# board.net
KiCad netlist of a schematic drawn in EAGLE
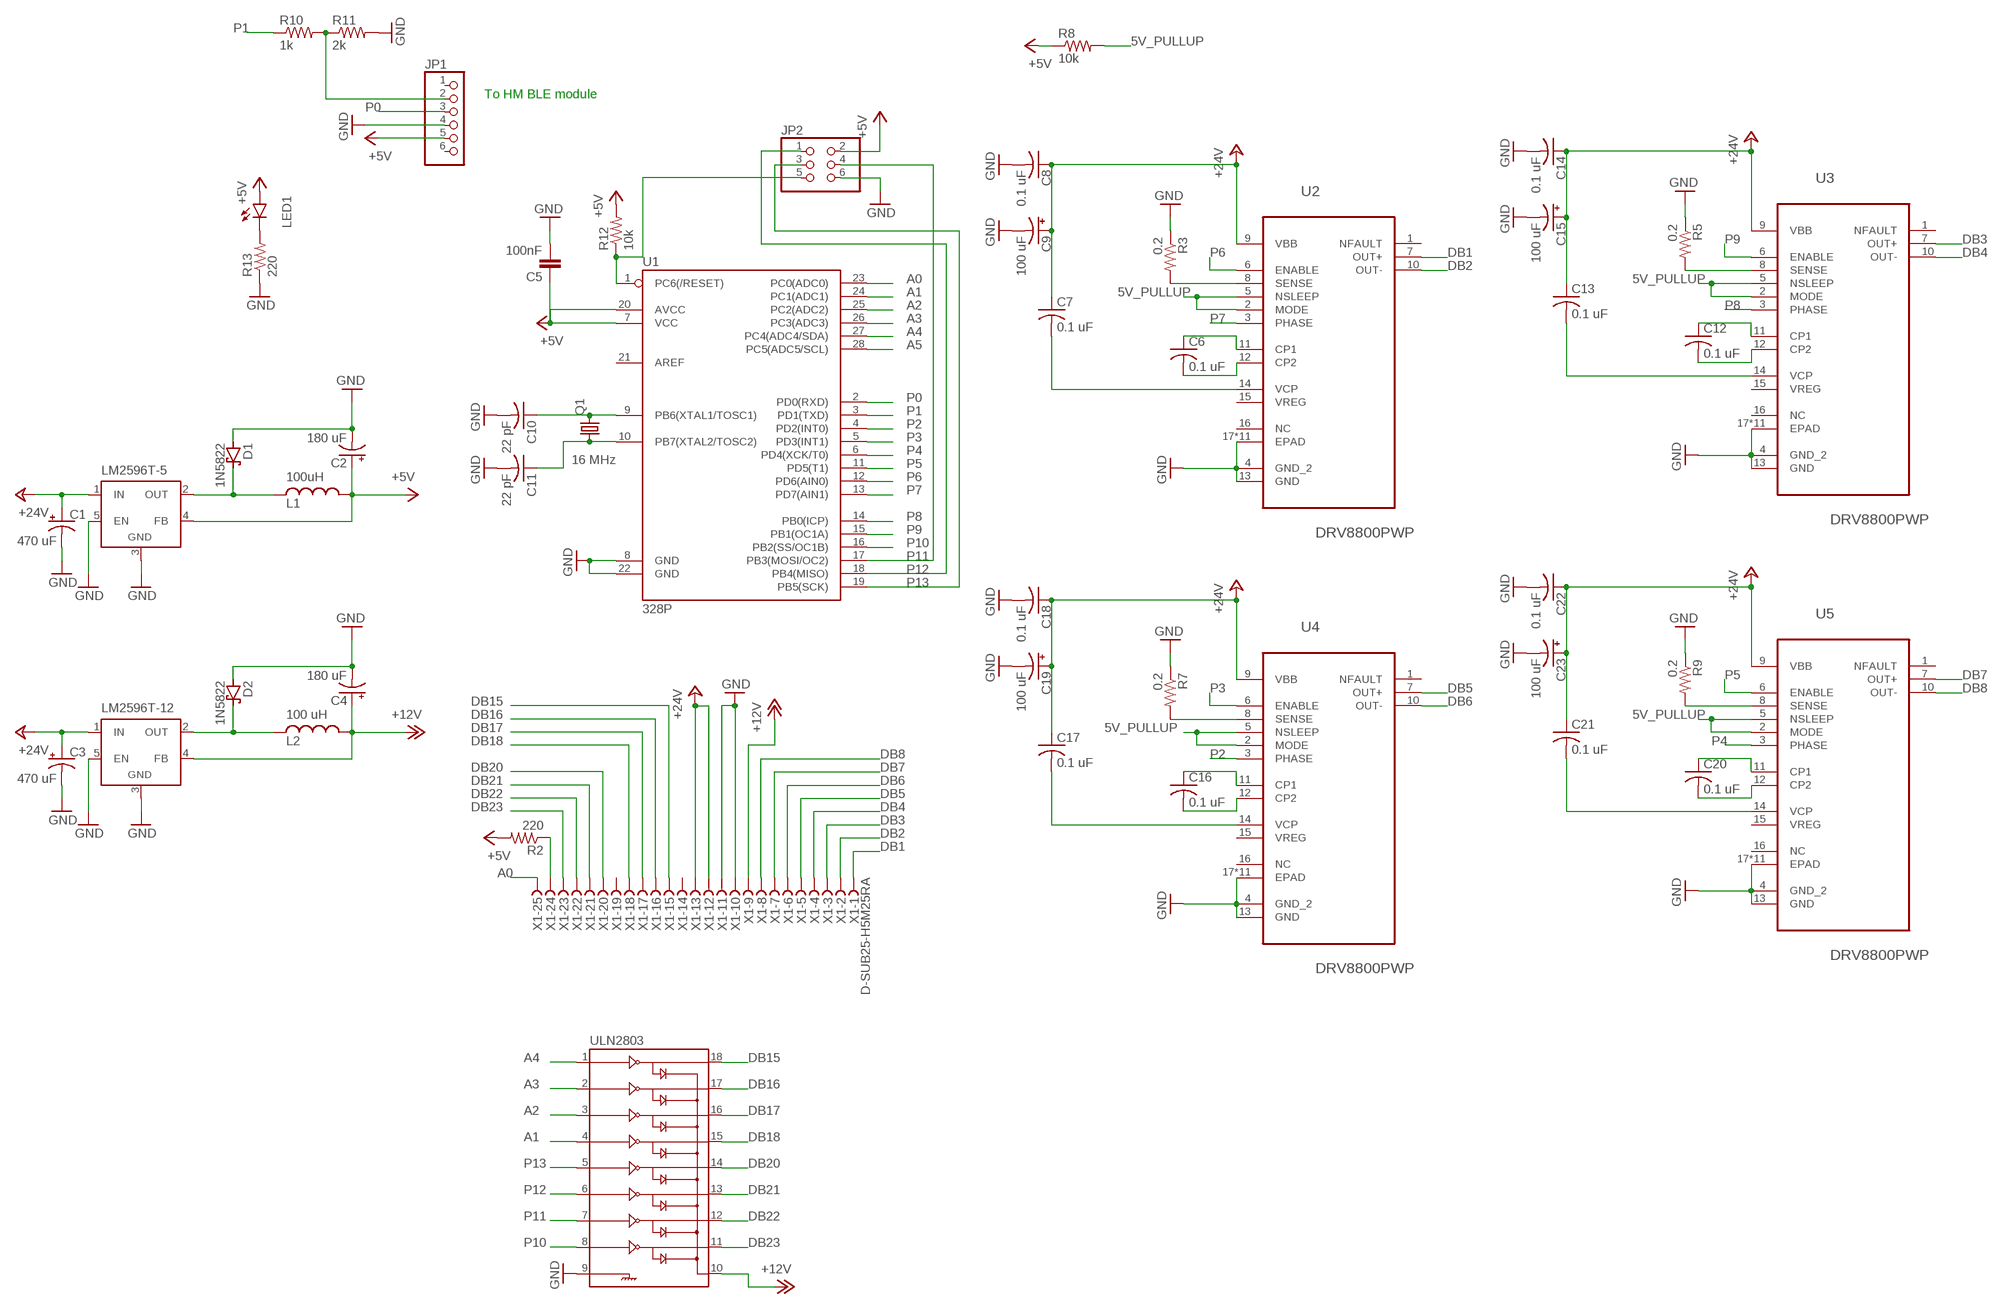
[diagram p0: schematic, sheet 1]

(export (version "E")
  (design (tool "Eeschema 10.0.6"))
  (components
    (comp (ref "C1")
      (value "470 uF")
      (footprint "eagle-import:E3,5-8")
      (libsource (lib "eagle-import") (part "CPOL-USE3.5-8"))
    )
    (comp (ref "C2")
      (value "180 uF")
      (footprint "eagle-import:E3,5-8")
      (libsource (lib "eagle-import") (part "CPOL-USE3.5-8"))
    )
    (comp (ref "C3")
      (value "470 uF")
      (footprint "eagle-import:E3,5-8")
      (libsource (lib "eagle-import") (part "CPOL-USE3.5-8"))
    )
    (comp (ref "C4")
      (value "180 uF")
      (footprint "eagle-import:E3,5-8")
      (libsource (lib "eagle-import") (part "CPOL-USE3.5-8"))
    )
    (comp (ref "C5")
      (value "100nF")
      (footprint "eagle-import:C0805")
      (libsource (lib "eagle-import") (part "C-EUC0805"))
    )
    (comp (ref "C6")
      (value "0.1 uF")
      (footprint "eagle-import:C0805")
      (libsource (lib "eagle-import") (part "C-USC0805"))
    )
    (comp (ref "C7")
      (value "0.1 uF")
      (footprint "eagle-import:C0805")
      (libsource (lib "eagle-import") (part "C-USC0805"))
    )
    (comp (ref "C8")
      (value "0.1 uF")
      (footprint "eagle-import:C0805")
      (libsource (lib "eagle-import") (part "C-USC0805"))
    )
    (comp (ref "C9")
      (value "100 uF")
      (footprint "eagle-import:E3,5-8")
      (libsource (lib "eagle-import") (part "CPOL-USE3.5-8"))
    )
    (comp (ref "C10")
      (value "22 pF")
      (footprint "eagle-import:C0805")
      (libsource (lib "eagle-import") (part "C-USC0805"))
    )
    (comp (ref "C11")
      (value "22 pF")
      (footprint "eagle-import:C0805")
      (libsource (lib "eagle-import") (part "C-USC0805"))
    )
    (comp (ref "C12")
      (value "0.1 uF")
      (footprint "eagle-import:C0805")
      (libsource (lib "eagle-import") (part "C-USC0805"))
    )
    (comp (ref "C13")
      (value "0.1 uF")
      (footprint "eagle-import:C0805")
      (libsource (lib "eagle-import") (part "C-USC0805"))
    )
    (comp (ref "C14")
      (value "0.1 uF")
      (footprint "eagle-import:C0805")
      (libsource (lib "eagle-import") (part "C-USC0805"))
    )
    (comp (ref "C15")
      (value "100 uF")
      (footprint "eagle-import:E3,5-8")
      (libsource (lib "eagle-import") (part "CPOL-USE3.5-8"))
    )
    (comp (ref "C16")
      (value "0.1 uF")
      (footprint "eagle-import:C0805")
      (libsource (lib "eagle-import") (part "C-USC0805"))
    )
    (comp (ref "C17")
      (value "0.1 uF")
      (footprint "eagle-import:C0805")
      (libsource (lib "eagle-import") (part "C-USC0805"))
    )
    (comp (ref "C18")
      (value "0.1 uF")
      (footprint "eagle-import:C0805")
      (libsource (lib "eagle-import") (part "C-USC0805"))
    )
    (comp (ref "C19")
      (value "100 uF")
      (footprint "eagle-import:E3,5-8")
      (libsource (lib "eagle-import") (part "CPOL-USE3.5-8"))
    )
    (comp (ref "C20")
      (value "0.1 uF")
      (footprint "eagle-import:C0805")
      (libsource (lib "eagle-import") (part "C-USC0805"))
    )
    (comp (ref "C21")
      (value "0.1 uF")
      (footprint "eagle-import:C0805")
      (libsource (lib "eagle-import") (part "C-USC0805"))
    )
    (comp (ref "C22")
      (value "0.1 uF")
      (footprint "eagle-import:C0805")
      (libsource (lib "eagle-import") (part "C-USC0805"))
    )
    (comp (ref "C23")
      (value "100 uF")
      (footprint "eagle-import:E3,5-8")
      (libsource (lib "eagle-import") (part "CPOL-USE3.5-8"))
    )
    (comp (ref "D1")
      (value "1N5822")
      (footprint "eagle-import:DO201T15")
      (libsource (lib "eagle-import") (part "SCHOTTKY-DIODEDO201T15"))
    )
    (comp (ref "D2")
      (value "1N5822")
      (footprint "eagle-import:DO201T15")
      (libsource (lib "eagle-import") (part "SCHOTTKY-DIODEDO201T15"))
    )
    (comp (ref "JP1")
      (value "PINHD-1X6")
      (footprint "eagle-import:1X06")
      (libsource (lib "eagle-import") (part "PINHD-1X6"))
    )
    (comp (ref "JP2")
      (value "PINHD-2X3")
      (footprint "eagle-import:2X03")
      (libsource (lib "eagle-import") (part "PINHD-2X3"))
    )
    (comp (ref "L1")
      (value "100uH")
      (footprint "eagle-import:SRR1260")
      (libsource (lib "eagle-import") (part "SRR1260"))
    )
    (comp (ref "L2")
      (value "100 uH")
      (footprint "eagle-import:SRR1260")
      (libsource (lib "eagle-import") (part "SRR1260"))
    )
    (comp (ref "LED1")
      (value "LED5MM")
      (footprint "eagle-import:LED5MM")
      (libsource (lib "eagle-import") (part "LED5MM"))
    )
    (comp (ref "LM2596T-5")
      (value "LM2596TV")
      (footprint "eagle-import:TO220-51")
      (libsource (lib "eagle-import") (part "LM2596TV"))
    )
    (comp (ref "LM2596T-12")
      (value "LM2596TV")
      (footprint "eagle-import:TO220-51")
      (libsource (lib "eagle-import") (part "LM2596TV"))
    )
    (comp (ref "Q1")
      (value "16 MHz")
      (footprint "eagle-import:HC49_S")
      (libsource (lib "eagle-import") (part "CRYSTALHC49S"))
    )
    (comp (ref "R2")
      (value "220")
      (footprint "eagle-import:R0805")
      (libsource (lib "eagle-import") (part "R-US_R0805"))
    )
    (comp (ref "R3")
      (value "0.2")
      (footprint "eagle-import:R0805")
      (libsource (lib "eagle-import") (part "R-US_R0805"))
    )
    (comp (ref "R5")
      (value "0.2")
      (footprint "eagle-import:R0805")
      (libsource (lib "eagle-import") (part "R-US_R0805"))
    )
    (comp (ref "R7")
      (value "0.2")
      (footprint "eagle-import:R0805")
      (libsource (lib "eagle-import") (part "R-US_R0805"))
    )
    (comp (ref "R8")
      (value "10k")
      (footprint "eagle-import:R0805")
      (libsource (lib "eagle-import") (part "R-US_R0805"))
    )
    (comp (ref "R9")
      (value "0.2")
      (footprint "eagle-import:R0805")
      (libsource (lib "eagle-import") (part "R-US_R0805"))
    )
    (comp (ref "R10")
      (value "1k")
      (footprint "eagle-import:R0805")
      (libsource (lib "eagle-import") (part "R-US_R0805"))
    )
    (comp (ref "R11")
      (value "2k")
      (footprint "eagle-import:R0805")
      (libsource (lib "eagle-import") (part "R-US_R0805"))
    )
    (comp (ref "R12")
      (value "10k")
      (footprint "eagle-import:R0805")
      (libsource (lib "eagle-import") (part "R-US_R0805"))
    )
    (comp (ref "R13")
      (value "220")
      (footprint "eagle-import:R0805")
      (libsource (lib "eagle-import") (part "R-US_R0805"))
    )
    (comp (ref "U1")
      (value "328P")
      (footprint "eagle-import:DIP28")
      (libsource (lib "eagle-import") (part "ATMEGA328P_PDIP"))
    )
    (comp (ref "U2")
      (value "DRV8800PWP")
      (footprint "eagle-import:SOP65P640X120-17N")
      (libsource (lib "eagle-import") (part "DRV8800PWP"))
    )
    (comp (ref "U3")
      (value "DRV8800PWP")
      (footprint "eagle-import:SOP65P640X120-17N")
      (libsource (lib "eagle-import") (part "DRV8800PWP"))
    )
    (comp (ref "U4")
      (value "DRV8800PWP")
      (footprint "eagle-import:SOP65P640X120-17N")
      (libsource (lib "eagle-import") (part "DRV8800PWP"))
    )
    (comp (ref "U5")
      (value "DRV8800PWP")
      (footprint "eagle-import:SOP65P640X120-17N")
      (libsource (lib "eagle-import") (part "DRV8800PWP"))
    )
    (comp (ref "ULN2803")
      (value "ULN2803DIP")
      (footprint "eagle-import:DIL18")
      (libsource (lib "eagle-import") (part "ULN2803DIP"))
    )
    (comp (ref "X1")
      (value "D-SUB25-H5M25RA")
      (footprint "eagle-import:H5M25RA")
      (fields (field (name "MPN") "H5M25RA29CS"))
      (libsource (lib "eagle-import") (part "D-SUB25-H5M25RA"))
    )
  )
  (nets
    (net (code "1") (name "+5V") (class "Default")
      (node (ref "C2") (pin "+") (pinfunction "+_+") (pintype "passive"))
      (node (ref "C5") (pin "1") (pinfunction "1_1") (pintype "passive"))
      (node (ref "JP1") (pin "5") (pinfunction "5_5") (pintype "passive"))
      (node (ref "JP2") (pin "2") (pinfunction "2_2") (pintype "passive"))
      (node (ref "L1") (pin "2") (pinfunction "2_2") (pintype "passive"))
      (node (ref "LED1") (pin "A") (pinfunction "A_A") (pintype "passive"))
      (node (ref "LM2596T-5") (pin "4") (pinfunction "FB_4") (pintype "input"))
      (node (ref "R12") (pin "2") (pinfunction "2_2") (pintype "passive"))
      (node (ref "R2") (pin "2") (pinfunction "2_2") (pintype "passive"))
      (node (ref "R8") (pin "1") (pinfunction "1_1") (pintype "passive"))
      (node (ref "U1") (pin "20") (pinfunction "AVCC_20") (pintype "bidirectional"))
      (node (ref "U1") (pin "7") (pinfunction "VCC_7") (pintype "bidirectional"))
    )
    (net (code "2") (name "+12V") (class "Default")
      (node (ref "C4") (pin "+") (pinfunction "+_+") (pintype "passive"))
      (node (ref "L2") (pin "2") (pinfunction "2_2") (pintype "passive"))
      (node (ref "LM2596T-12") (pin "4") (pinfunction "FB_4") (pintype "input"))
      (node (ref "ULN2803") (pin "10") (pinfunction "10_10") (pintype "bidirectional"))
      (node (ref "X1") (pin "9") (pinfunction "F_9") (pintype "passive"))
    )
    (net (code "3") (name "+24V") (class "Default")
      (node (ref "C1") (pin "+") (pinfunction "+_+") (pintype "passive"))
      (node (ref "C13") (pin "1") (pinfunction "1_1") (pintype "passive"))
      (node (ref "C14") (pin "1") (pinfunction "1_1") (pintype "passive"))
      (node (ref "C15") (pin "+") (pinfunction "+_+") (pintype "passive"))
      (node (ref "C17") (pin "1") (pinfunction "1_1") (pintype "passive"))
      (node (ref "C18") (pin "1") (pinfunction "1_1") (pintype "passive"))
      (node (ref "C19") (pin "+") (pinfunction "+_+") (pintype "passive"))
      (node (ref "C21") (pin "1") (pinfunction "1_1") (pintype "passive"))
      (node (ref "C22") (pin "1") (pinfunction "1_1") (pintype "passive"))
      (node (ref "C23") (pin "+") (pinfunction "+_+") (pintype "passive"))
      (node (ref "C3") (pin "+") (pinfunction "+_+") (pintype "passive"))
      (node (ref "C7") (pin "1") (pinfunction "1_1") (pintype "passive"))
      (node (ref "C8") (pin "1") (pinfunction "1_1") (pintype "passive"))
      (node (ref "C9") (pin "+") (pinfunction "+_+") (pintype "passive"))
      (node (ref "LM2596T-12") (pin "1") (pinfunction "IN_1") (pintype "input"))
      (node (ref "LM2596T-5") (pin "1") (pinfunction "IN_1") (pintype "input"))
      (node (ref "U2") (pin "9") (pinfunction "VBB_9") (pintype "power_in"))
      (node (ref "U3") (pin "9") (pinfunction "VBB_9") (pintype "power_in"))
      (node (ref "U4") (pin "9") (pinfunction "VBB_9") (pintype "power_in"))
      (node (ref "U5") (pin "9") (pinfunction "VBB_9") (pintype "power_in"))
      (node (ref "X1") (pin "12") (pinfunction "F_12") (pintype "passive"))
      (node (ref "X1") (pin "13") (pinfunction "F_13") (pintype "passive"))
    )
    (net (code "4") (name "/5V_PULLUP") (class "Default")
      (node (ref "R8") (pin "2") (pinfunction "2_2") (pintype "passive"))
      (node (ref "U2") (pin "2") (pinfunction "MODE_2") (pintype "input"))
      (node (ref "U2") (pin "5") (pinfunction "NSLEEP_5") (pintype "input"))
      (node (ref "U3") (pin "2") (pinfunction "MODE_2") (pintype "input"))
      (node (ref "U3") (pin "5") (pinfunction "NSLEEP_5") (pintype "input"))
      (node (ref "U4") (pin "2") (pinfunction "MODE_2") (pintype "input"))
      (node (ref "U4") (pin "5") (pinfunction "NSLEEP_5") (pintype "input"))
      (node (ref "U5") (pin "2") (pinfunction "MODE_2") (pintype "input"))
      (node (ref "U5") (pin "5") (pinfunction "NSLEEP_5") (pintype "input"))
    )
    (net (code "5") (name "/A0") (class "Default")
      (node (ref "U1") (pin "23") (pinfunction "PC0(ADC0)_23") (pintype "bidirectional"))
      (node (ref "X1") (pin "25") (pinfunction "F_25") (pintype "passive"))
    )
    (net (code "6") (name "/A1") (class "Default")
      (node (ref "U1") (pin "24") (pinfunction "PC1(ADC1)_24") (pintype "bidirectional"))
      (node (ref "ULN2803") (pin "4") (pinfunction "4_4") (pintype "bidirectional"))
    )
    (net (code "7") (name "/A2") (class "Default")
      (node (ref "U1") (pin "25") (pinfunction "PC2(ADC2)_25") (pintype "bidirectional"))
      (node (ref "ULN2803") (pin "3") (pinfunction "3_3") (pintype "bidirectional"))
    )
    (net (code "8") (name "/A3") (class "Default")
      (node (ref "U1") (pin "26") (pinfunction "PC3(ADC3)_26") (pintype "bidirectional"))
      (node (ref "ULN2803") (pin "2") (pinfunction "2_2") (pintype "bidirectional"))
    )
    (net (code "9") (name "/A4") (class "Default")
      (node (ref "U1") (pin "27") (pinfunction "PC4(ADC4/SDA)_27") (pintype "bidirectional"))
      (node (ref "ULN2803") (pin "1") (pinfunction "1_1") (pintype "bidirectional"))
    )
    (net (code "10") (name "/A5") (class "Default")
      (node (ref "U1") (pin "28") (pinfunction "PC5(ADC5/SCL)_28") (pintype "bidirectional"))
    )
    (net (code "11") (name "/DB1") (class "Default")
      (node (ref "U2") (pin "7") (pinfunction "OUT+_7") (pintype "output"))
      (node (ref "X1") (pin "1") (pinfunction "F_1") (pintype "passive"))
    )
    (net (code "12") (name "/DB2") (class "Default")
      (node (ref "U2") (pin "10") (pinfunction "OUT-_10") (pintype "output"))
      (node (ref "X1") (pin "2") (pinfunction "F_2") (pintype "passive"))
    )
    (net (code "13") (name "/DB3") (class "Default")
      (node (ref "U3") (pin "7") (pinfunction "OUT+_7") (pintype "output"))
      (node (ref "X1") (pin "3") (pinfunction "F_3") (pintype "passive"))
    )
    (net (code "14") (name "/DB4") (class "Default")
      (node (ref "U3") (pin "10") (pinfunction "OUT-_10") (pintype "output"))
      (node (ref "X1") (pin "4") (pinfunction "F_4") (pintype "passive"))
    )
    (net (code "15") (name "/DB5") (class "Default")
      (node (ref "U4") (pin "7") (pinfunction "OUT+_7") (pintype "output"))
      (node (ref "X1") (pin "5") (pinfunction "F_5") (pintype "passive"))
    )
    (net (code "16") (name "/DB6") (class "Default")
      (node (ref "U4") (pin "10") (pinfunction "OUT-_10") (pintype "output"))
      (node (ref "X1") (pin "6") (pinfunction "F_6") (pintype "passive"))
    )
    (net (code "17") (name "/DB7") (class "Default")
      (node (ref "U5") (pin "7") (pinfunction "OUT+_7") (pintype "output"))
      (node (ref "X1") (pin "7") (pinfunction "F_7") (pintype "passive"))
    )
    (net (code "18") (name "/DB8") (class "Default")
      (node (ref "U5") (pin "10") (pinfunction "OUT-_10") (pintype "output"))
      (node (ref "X1") (pin "8") (pinfunction "F_8") (pintype "passive"))
    )
    (net (code "19") (name "/DB15") (class "Default")
      (node (ref "ULN2803") (pin "18") (pinfunction "18_18") (pintype "bidirectional"))
      (node (ref "X1") (pin "15") (pinfunction "F_15") (pintype "passive"))
    )
    (net (code "20") (name "/DB16") (class "Default")
      (node (ref "ULN2803") (pin "17") (pinfunction "17_17") (pintype "bidirectional"))
      (node (ref "X1") (pin "16") (pinfunction "F_16") (pintype "passive"))
    )
    (net (code "21") (name "/DB17") (class "Default")
      (node (ref "ULN2803") (pin "16") (pinfunction "16_16") (pintype "bidirectional"))
      (node (ref "X1") (pin "17") (pinfunction "F_17") (pintype "passive"))
    )
    (net (code "22") (name "/DB18") (class "Default")
      (node (ref "ULN2803") (pin "15") (pinfunction "15_15") (pintype "bidirectional"))
      (node (ref "X1") (pin "18") (pinfunction "F_18") (pintype "passive"))
    )
    (net (code "23") (name "/DB20") (class "Default")
      (node (ref "ULN2803") (pin "14") (pinfunction "14_14") (pintype "bidirectional"))
      (node (ref "X1") (pin "20") (pinfunction "F_20") (pintype "passive"))
    )
    (net (code "24") (name "/DB21") (class "Default")
      (node (ref "ULN2803") (pin "13") (pinfunction "13_13") (pintype "bidirectional"))
      (node (ref "X1") (pin "21") (pinfunction "F_21") (pintype "passive"))
    )
    (net (code "25") (name "/DB22") (class "Default")
      (node (ref "ULN2803") (pin "12") (pinfunction "12_12") (pintype "bidirectional"))
      (node (ref "X1") (pin "22") (pinfunction "F_22") (pintype "passive"))
    )
    (net (code "26") (name "/DB23") (class "Default")
      (node (ref "ULN2803") (pin "11") (pinfunction "11_11") (pintype "bidirectional"))
      (node (ref "X1") (pin "23") (pinfunction "F_23") (pintype "passive"))
    )
    (net (code "27") (name "/P0") (class "Default")
      (node (ref "JP1") (pin "3") (pinfunction "3_3") (pintype "passive"))
      (node (ref "U1") (pin "2") (pinfunction "PD0(RXD)_2") (pintype "bidirectional"))
    )
    (net (code "28") (name "/P1") (class "Default")
      (node (ref "R10") (pin "1") (pinfunction "1_1") (pintype "passive"))
      (node (ref "U1") (pin "3") (pinfunction "PD1(TXD)_3") (pintype "bidirectional"))
    )
    (net (code "29") (name "/P2") (class "Default")
      (node (ref "U1") (pin "4") (pinfunction "PD2(INT0)_4") (pintype "bidirectional"))
      (node (ref "U4") (pin "3") (pinfunction "PHASE_3") (pintype "input"))
    )
    (net (code "30") (name "/P3") (class "Default")
      (node (ref "U1") (pin "5") (pinfunction "PD3(INT1)_5") (pintype "bidirectional"))
      (node (ref "U4") (pin "6") (pinfunction "ENABLE_6") (pintype "input"))
    )
    (net (code "31") (name "/P4") (class "Default")
      (node (ref "U1") (pin "6") (pinfunction "PD4(XCK/T0)_6") (pintype "bidirectional"))
      (node (ref "U5") (pin "3") (pinfunction "PHASE_3") (pintype "input"))
    )
    (net (code "32") (name "/P5") (class "Default")
      (node (ref "U1") (pin "11") (pinfunction "PD5(T1)_11") (pintype "bidirectional"))
      (node (ref "U5") (pin "6") (pinfunction "ENABLE_6") (pintype "input"))
    )
    (net (code "33") (name "/P6") (class "Default")
      (node (ref "U1") (pin "12") (pinfunction "PD6(AIN0)_12") (pintype "bidirectional"))
      (node (ref "U2") (pin "6") (pinfunction "ENABLE_6") (pintype "input"))
    )
    (net (code "34") (name "/P7") (class "Default")
      (node (ref "U1") (pin "13") (pinfunction "PD7(AIN1)_13") (pintype "bidirectional"))
      (node (ref "U2") (pin "3") (pinfunction "PHASE_3") (pintype "input"))
    )
    (net (code "35") (name "/P8") (class "Default")
      (node (ref "U1") (pin "14") (pinfunction "PB0(ICP)_14") (pintype "bidirectional"))
      (node (ref "U3") (pin "3") (pinfunction "PHASE_3") (pintype "input"))
    )
    (net (code "36") (name "/P9") (class "Default")
      (node (ref "U1") (pin "15") (pinfunction "PB1(OC1A)_15") (pintype "bidirectional"))
      (node (ref "U3") (pin "6") (pinfunction "ENABLE_6") (pintype "input"))
    )
    (net (code "37") (name "/P10") (class "Default")
      (node (ref "U1") (pin "16") (pinfunction "PB2(SS/OC1B)_16") (pintype "bidirectional"))
      (node (ref "ULN2803") (pin "8") (pinfunction "8_8") (pintype "bidirectional"))
    )
    (net (code "38") (name "/P11") (class "Default")
      (node (ref "JP2") (pin "4") (pinfunction "4_4") (pintype "passive"))
      (node (ref "U1") (pin "17") (pinfunction "PB3(MOSI/OC2)_17") (pintype "bidirectional"))
      (node (ref "ULN2803") (pin "7") (pinfunction "7_7") (pintype "bidirectional"))
    )
    (net (code "39") (name "/P12") (class "Default")
      (node (ref "JP2") (pin "1") (pinfunction "1_1") (pintype "passive"))
      (node (ref "U1") (pin "18") (pinfunction "PB4(MISO)_18") (pintype "bidirectional"))
      (node (ref "ULN2803") (pin "6") (pinfunction "6_6") (pintype "bidirectional"))
    )
    (net (code "40") (name "/P13") (class "Default")
      (node (ref "JP2") (pin "3") (pinfunction "3_3") (pintype "passive"))
      (node (ref "U1") (pin "19") (pinfunction "PB5(SCK)_19") (pintype "bidirectional"))
      (node (ref "ULN2803") (pin "5") (pinfunction "5_5") (pintype "bidirectional"))
    )
    (net (code "41") (name "GND") (class "Default")
      (node (ref "C1") (pin "-") (pinfunction "-_-") (pintype "passive"))
      (node (ref "C10") (pin "2") (pinfunction "2_2") (pintype "passive"))
      (node (ref "C11") (pin "2") (pinfunction "2_2") (pintype "passive"))
      (node (ref "C14") (pin "2") (pinfunction "2_2") (pintype "passive"))
      (node (ref "C15") (pin "-") (pinfunction "-_-") (pintype "passive"))
      (node (ref "C18") (pin "2") (pinfunction "2_2") (pintype "passive"))
      (node (ref "C19") (pin "-") (pinfunction "-_-") (pintype "passive"))
      (node (ref "C2") (pin "-") (pinfunction "-_-") (pintype "passive"))
      (node (ref "C22") (pin "2") (pinfunction "2_2") (pintype "passive"))
      (node (ref "C23") (pin "-") (pinfunction "-_-") (pintype "passive"))
      (node (ref "C3") (pin "-") (pinfunction "-_-") (pintype "passive"))
      (node (ref "C4") (pin "-") (pinfunction "-_-") (pintype "passive"))
      (node (ref "C5") (pin "2") (pinfunction "2_2") (pintype "passive"))
      (node (ref "C8") (pin "2") (pinfunction "2_2") (pintype "passive"))
      (node (ref "C9") (pin "-") (pinfunction "-_-") (pintype "passive"))
      (node (ref "D1") (pin "A") (pinfunction "A_A") (pintype "passive"))
      (node (ref "D2") (pin "A") (pinfunction "A_A") (pintype "passive"))
      (node (ref "JP1") (pin "4") (pinfunction "4_4") (pintype "passive"))
      (node (ref "JP2") (pin "6") (pinfunction "6_6") (pintype "passive"))
      (node (ref "LM2596T-12") (pin "3") (pinfunction "GND_3") (pintype "power_in"))
      (node (ref "LM2596T-12") (pin "5") (pinfunction "EN_5") (pintype "input"))
      (node (ref "LM2596T-5") (pin "3") (pinfunction "GND_3") (pintype "power_in"))
      (node (ref "LM2596T-5") (pin "5") (pinfunction "EN_5") (pintype "input"))
      (node (ref "R11") (pin "2") (pinfunction "2_2") (pintype "passive"))
      (node (ref "R13") (pin "1") (pinfunction "1_1") (pintype "passive"))
      (node (ref "R3") (pin "1") (pinfunction "1_1") (pintype "passive"))
      (node (ref "R5") (pin "1") (pinfunction "1_1") (pintype "passive"))
      (node (ref "R7") (pin "1") (pinfunction "1_1") (pintype "passive"))
      (node (ref "R9") (pin "1") (pinfunction "1_1") (pintype "passive"))
      (node (ref "U1") (pin "22") (pinfunction "GND_22") (pintype "bidirectional"))
      (node (ref "U1") (pin "8") (pinfunction "GND_8") (pintype "bidirectional"))
      (node (ref "U2") (pin "13") (pinfunction "GND_13") (pintype "passive"))
      (node (ref "U2") (pin "17") (pinfunction "EPAD_17") (pintype "passive"))
      (node (ref "U2") (pin "18") (pinfunction "EPAD_18") (pintype "passive"))
      (node (ref "U2") (pin "4") (pinfunction "GND_2_4") (pintype "passive"))
      (node (ref "U2") (pin "P$1") (pinfunction "EPAD_P$1") (pintype "passive"))
      (node (ref "U2") (pin "P$2") (pinfunction "EPAD_P$2") (pintype "passive"))
      (node (ref "U2") (pin "P$3") (pinfunction "EPAD_P$3") (pintype "passive"))
      (node (ref "U2") (pin "P$4") (pinfunction "EPAD_P$4") (pintype "passive"))
      (node (ref "U2") (pin "P$5") (pinfunction "EPAD_P$5") (pintype "passive"))
      (node (ref "U2") (pin "P$6") (pinfunction "EPAD_P$6") (pintype "passive"))
      (node (ref "U2") (pin "P$7") (pinfunction "EPAD_P$7") (pintype "passive"))
      (node (ref "U2") (pin "P$8") (pinfunction "EPAD_P$8") (pintype "passive"))
      (node (ref "U2") (pin "P$9") (pinfunction "EPAD_P$9") (pintype "passive"))
      (node (ref "U3") (pin "13") (pinfunction "GND_13") (pintype "passive"))
      (node (ref "U3") (pin "17") (pinfunction "EPAD_17") (pintype "passive"))
      (node (ref "U3") (pin "18") (pinfunction "EPAD_18") (pintype "passive"))
      (node (ref "U3") (pin "4") (pinfunction "GND_2_4") (pintype "passive"))
      (node (ref "U3") (pin "P$1") (pinfunction "EPAD_P$1") (pintype "passive"))
      (node (ref "U3") (pin "P$2") (pinfunction "EPAD_P$2") (pintype "passive"))
      (node (ref "U3") (pin "P$3") (pinfunction "EPAD_P$3") (pintype "passive"))
      (node (ref "U3") (pin "P$4") (pinfunction "EPAD_P$4") (pintype "passive"))
      (node (ref "U3") (pin "P$5") (pinfunction "EPAD_P$5") (pintype "passive"))
      (node (ref "U3") (pin "P$6") (pinfunction "EPAD_P$6") (pintype "passive"))
      (node (ref "U3") (pin "P$7") (pinfunction "EPAD_P$7") (pintype "passive"))
      (node (ref "U3") (pin "P$8") (pinfunction "EPAD_P$8") (pintype "passive"))
      (node (ref "U3") (pin "P$9") (pinfunction "EPAD_P$9") (pintype "passive"))
      (node (ref "U4") (pin "13") (pinfunction "GND_13") (pintype "passive"))
      (node (ref "U4") (pin "17") (pinfunction "EPAD_17") (pintype "passive"))
      (node (ref "U4") (pin "18") (pinfunction "EPAD_18") (pintype "passive"))
      (node (ref "U4") (pin "4") (pinfunction "GND_2_4") (pintype "passive"))
      (node (ref "U4") (pin "P$1") (pinfunction "EPAD_P$1") (pintype "passive"))
      (node (ref "U4") (pin "P$2") (pinfunction "EPAD_P$2") (pintype "passive"))
      (node (ref "U4") (pin "P$3") (pinfunction "EPAD_P$3") (pintype "passive"))
      (node (ref "U4") (pin "P$4") (pinfunction "EPAD_P$4") (pintype "passive"))
      (node (ref "U4") (pin "P$5") (pinfunction "EPAD_P$5") (pintype "passive"))
      (node (ref "U4") (pin "P$6") (pinfunction "EPAD_P$6") (pintype "passive"))
      (node (ref "U4") (pin "P$7") (pinfunction "EPAD_P$7") (pintype "passive"))
      (node (ref "U4") (pin "P$8") (pinfunction "EPAD_P$8") (pintype "passive"))
      (node (ref "U4") (pin "P$9") (pinfunction "EPAD_P$9") (pintype "passive"))
      (node (ref "U5") (pin "13") (pinfunction "GND_13") (pintype "passive"))
      (node (ref "U5") (pin "17") (pinfunction "EPAD_17") (pintype "passive"))
      (node (ref "U5") (pin "18") (pinfunction "EPAD_18") (pintype "passive"))
      (node (ref "U5") (pin "4") (pinfunction "GND_2_4") (pintype "passive"))
      (node (ref "U5") (pin "P$1") (pinfunction "EPAD_P$1") (pintype "passive"))
      (node (ref "U5") (pin "P$2") (pinfunction "EPAD_P$2") (pintype "passive"))
      (node (ref "U5") (pin "P$3") (pinfunction "EPAD_P$3") (pintype "passive"))
      (node (ref "U5") (pin "P$4") (pinfunction "EPAD_P$4") (pintype "passive"))
      (node (ref "U5") (pin "P$5") (pinfunction "EPAD_P$5") (pintype "passive"))
      (node (ref "U5") (pin "P$6") (pinfunction "EPAD_P$6") (pintype "passive"))
      (node (ref "U5") (pin "P$7") (pinfunction "EPAD_P$7") (pintype "passive"))
      (node (ref "U5") (pin "P$8") (pinfunction "EPAD_P$8") (pintype "passive"))
      (node (ref "U5") (pin "P$9") (pinfunction "EPAD_P$9") (pintype "passive"))
      (node (ref "ULN2803") (pin "9") (pinfunction "9_9") (pintype "bidirectional"))
      (node (ref "X1") (pin "10") (pinfunction "F_10") (pintype "passive"))
      (node (ref "X1") (pin "11") (pinfunction "F_11") (pintype "passive"))
    )
    (net (code "42") (name "Net-(JP1-Pad2)") (class "Default")
      (node (ref "JP1") (pin "2") (pinfunction "2_2") (pintype "passive"))
      (node (ref "R10") (pin "2") (pinfunction "2_2") (pintype "passive"))
      (node (ref "R11") (pin "1") (pinfunction "1_1") (pintype "passive"))
    )
    (net (code "43") (name "Net-(LED1-C)") (class "Default")
      (node (ref "LED1") (pin "K") (pinfunction "C_K") (pintype "passive"))
      (node (ref "R13") (pin "2") (pinfunction "2_2") (pintype "passive"))
    )
    (net (code "44") (name "Net-(LM2596T-5-OUT)") (class "Default")
      (node (ref "D1") (pin "C") (pinfunction "C_C") (pintype "passive"))
      (node (ref "L1") (pin "1") (pinfunction "1_1") (pintype "passive"))
      (node (ref "LM2596T-5") (pin "2") (pinfunction "OUT_2") (pintype "output"))
    )
    (net (code "45") (name "Net-(LM2596T-12-OUT)") (class "Default")
      (node (ref "D2") (pin "C") (pinfunction "C_C") (pintype "passive"))
      (node (ref "L2") (pin "1") (pinfunction "1_1") (pintype "passive"))
      (node (ref "LM2596T-12") (pin "2") (pinfunction "OUT_2") (pintype "output"))
    )
    (net (code "46") (name "Net-(U1-PB6(XTAL1{slash}TOSC1))") (class "Default")
      (node (ref "C10") (pin "1") (pinfunction "1_1") (pintype "passive"))
      (node (ref "Q1") (pin "2") (pinfunction "2_2") (pintype "passive"))
      (node (ref "U1") (pin "9") (pinfunction "PB6(XTAL1/TOSC1)_9") (pintype "bidirectional"))
    )
    (net (code "47") (name "Net-(U1-PB7(XTAL2{slash}TOSC2))") (class "Default")
      (node (ref "C11") (pin "1") (pinfunction "1_1") (pintype "passive"))
      (node (ref "Q1") (pin "1") (pinfunction "1_1") (pintype "passive"))
      (node (ref "U1") (pin "10") (pinfunction "PB7(XTAL2/TOSC2)_10") (pintype "bidirectional"))
    )
    (net (code "48") (name "Net-(U1-PC6({slash}RESET))") (class "Default")
      (node (ref "JP2") (pin "5") (pinfunction "5_5") (pintype "passive"))
      (node (ref "R12") (pin "1") (pinfunction "1_1") (pintype "passive"))
      (node (ref "U1") (pin "1") (pinfunction "PC6(/RESET)_1") (pintype "bidirectional"))
    )
    (net (code "49") (name "Net-(U2-CP1)") (class "Default")
      (node (ref "C6") (pin "1") (pinfunction "1_1") (pintype "passive"))
      (node (ref "U2") (pin "11") (pinfunction "CP1_11") (pintype "passive"))
    )
    (net (code "50") (name "Net-(U2-CP2)") (class "Default")
      (node (ref "C6") (pin "2") (pinfunction "2_2") (pintype "passive"))
      (node (ref "U2") (pin "12") (pinfunction "CP2_12") (pintype "passive"))
    )
    (net (code "51") (name "Net-(U2-SENSE)") (class "Default")
      (node (ref "R3") (pin "2") (pinfunction "2_2") (pintype "passive"))
      (node (ref "U2") (pin "8") (pinfunction "SENSE_8") (pintype "input"))
    )
    (net (code "52") (name "Net-(U2-VCP)") (class "Default")
      (node (ref "C7") (pin "2") (pinfunction "2_2") (pintype "passive"))
      (node (ref "U2") (pin "14") (pinfunction "VCP_14") (pintype "passive"))
    )
    (net (code "53") (name "Net-(U3-CP1)") (class "Default")
      (node (ref "C12") (pin "1") (pinfunction "1_1") (pintype "passive"))
      (node (ref "U3") (pin "11") (pinfunction "CP1_11") (pintype "passive"))
    )
    (net (code "54") (name "Net-(U3-CP2)") (class "Default")
      (node (ref "C12") (pin "2") (pinfunction "2_2") (pintype "passive"))
      (node (ref "U3") (pin "12") (pinfunction "CP2_12") (pintype "passive"))
    )
    (net (code "55") (name "Net-(U3-SENSE)") (class "Default")
      (node (ref "R5") (pin "2") (pinfunction "2_2") (pintype "passive"))
      (node (ref "U3") (pin "8") (pinfunction "SENSE_8") (pintype "input"))
    )
    (net (code "56") (name "Net-(U3-VCP)") (class "Default")
      (node (ref "C13") (pin "2") (pinfunction "2_2") (pintype "passive"))
      (node (ref "U3") (pin "14") (pinfunction "VCP_14") (pintype "passive"))
    )
    (net (code "57") (name "Net-(U4-CP1)") (class "Default")
      (node (ref "C16") (pin "1") (pinfunction "1_1") (pintype "passive"))
      (node (ref "U4") (pin "11") (pinfunction "CP1_11") (pintype "passive"))
    )
    (net (code "58") (name "Net-(U4-CP2)") (class "Default")
      (node (ref "C16") (pin "2") (pinfunction "2_2") (pintype "passive"))
      (node (ref "U4") (pin "12") (pinfunction "CP2_12") (pintype "passive"))
    )
    (net (code "59") (name "Net-(U4-SENSE)") (class "Default")
      (node (ref "R7") (pin "2") (pinfunction "2_2") (pintype "passive"))
      (node (ref "U4") (pin "8") (pinfunction "SENSE_8") (pintype "input"))
    )
    (net (code "60") (name "Net-(U4-VCP)") (class "Default")
      (node (ref "C17") (pin "2") (pinfunction "2_2") (pintype "passive"))
      (node (ref "U4") (pin "14") (pinfunction "VCP_14") (pintype "passive"))
    )
    (net (code "61") (name "Net-(U5-CP1)") (class "Default")
      (node (ref "C20") (pin "1") (pinfunction "1_1") (pintype "passive"))
      (node (ref "U5") (pin "11") (pinfunction "CP1_11") (pintype "passive"))
    )
    (net (code "62") (name "Net-(U5-CP2)") (class "Default")
      (node (ref "C20") (pin "2") (pinfunction "2_2") (pintype "passive"))
      (node (ref "U5") (pin "12") (pinfunction "CP2_12") (pintype "passive"))
    )
    (net (code "63") (name "Net-(U5-SENSE)") (class "Default")
      (node (ref "R9") (pin "2") (pinfunction "2_2") (pintype "passive"))
      (node (ref "U5") (pin "8") (pinfunction "SENSE_8") (pintype "input"))
    )
    (net (code "64") (name "Net-(U5-VCP)") (class "Default")
      (node (ref "C21") (pin "2") (pinfunction "2_2") (pintype "passive"))
      (node (ref "U5") (pin "14") (pinfunction "VCP_14") (pintype "passive"))
    )
    (net (code "65") (name "Net-(X1Q-F)") (class "Default")
      (node (ref "R2") (pin "1") (pinfunction "1_1") (pintype "passive"))
      (node (ref "X1") (pin "24") (pinfunction "F_24") (pintype "passive"))
    )
    (net (code "66") (name "unconnected-(JP1-Pad1)") (class "Default")
      (node (ref "JP1") (pin "1") (pinfunction "1_1") (pintype "passive"))
    )
    (net (code "67") (name "unconnected-(JP1-Pad6)") (class "Default")
      (node (ref "JP1") (pin "6") (pinfunction "6_6") (pintype "passive"))
    )
    (net (code "68") (name "unconnected-(U1-AREF-Pad21)") (class "Default")
      (node (ref "U1") (pin "21") (pinfunction "AREF_21") (pintype "bidirectional"))
    )
    (net (code "69") (name "unconnected-(U2-NC-Pad16)") (class "Default")
      (node (ref "U2") (pin "16") (pinfunction "NC_16") (pintype "no_connect"))
    )
    (net (code "70") (name "unconnected-(U2-NFAULT-Pad1)") (class "Default")
      (node (ref "U2") (pin "1") (pinfunction "NFAULT_1") (pintype "output"))
    )
    (net (code "71") (name "unconnected-(U2-VREG-Pad15)") (class "Default")
      (node (ref "U2") (pin "15") (pinfunction "VREG_15") (pintype "passive"))
    )
    (net (code "72") (name "unconnected-(U3-NC-Pad16)") (class "Default")
      (node (ref "U3") (pin "16") (pinfunction "NC_16") (pintype "no_connect"))
    )
    (net (code "73") (name "unconnected-(U3-NFAULT-Pad1)") (class "Default")
      (node (ref "U3") (pin "1") (pinfunction "NFAULT_1") (pintype "output"))
    )
    (net (code "74") (name "unconnected-(U3-VREG-Pad15)") (class "Default")
      (node (ref "U3") (pin "15") (pinfunction "VREG_15") (pintype "passive"))
    )
    (net (code "75") (name "unconnected-(U4-NC-Pad16)") (class "Default")
      (node (ref "U4") (pin "16") (pinfunction "NC_16") (pintype "no_connect"))
    )
    (net (code "76") (name "unconnected-(U4-NFAULT-Pad1)") (class "Default")
      (node (ref "U4") (pin "1") (pinfunction "NFAULT_1") (pintype "output"))
    )
    (net (code "77") (name "unconnected-(U4-VREG-Pad15)") (class "Default")
      (node (ref "U4") (pin "15") (pinfunction "VREG_15") (pintype "passive"))
    )
    (net (code "78") (name "unconnected-(U5-NC-Pad16)") (class "Default")
      (node (ref "U5") (pin "16") (pinfunction "NC_16") (pintype "no_connect"))
    )
    (net (code "79") (name "unconnected-(U5-NFAULT-Pad1)") (class "Default")
      (node (ref "U5") (pin "1") (pinfunction "NFAULT_1") (pintype "output"))
    )
    (net (code "80") (name "unconnected-(U5-VREG-Pad15)") (class "Default")
      (node (ref "U5") (pin "15") (pinfunction "VREG_15") (pintype "passive"))
    )
    (net (code "81") (name "unconnected-(X1F-F-Pad14)") (class "Default")
      (node (ref "X1") (pin "14") (pinfunction "F_14") (pintype "passive"))
    )
    (net (code "82") (name "unconnected-(X1K-F-Pad19)") (class "Default")
      (node (ref "X1") (pin "19") (pinfunction "F_19") (pintype "passive"))
    )
  )
)
